# SD.net
KiCad netlist of a schematic drawn in Altium Designer
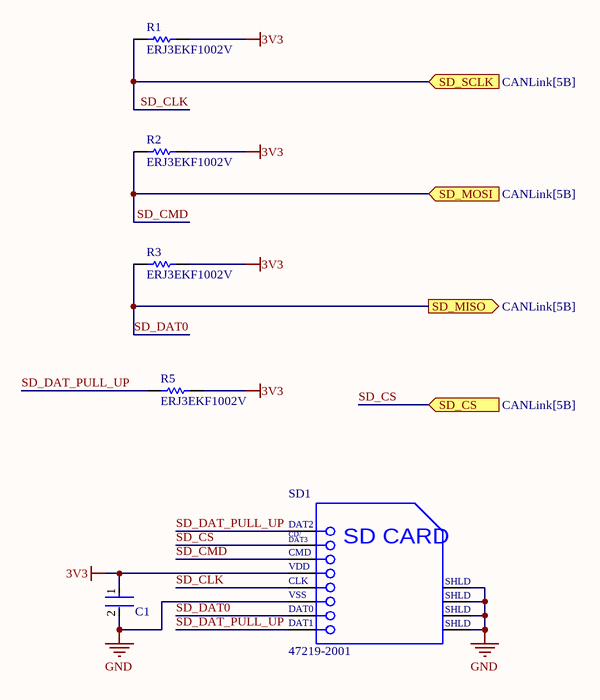
[diagram p0: SD.SchDoc]

(export (version "E")
  (design (tool "Eeschema 10.0.6"))
  (components
    (comp (ref "C1")
      (value "C0402C104K8PACTU")
      (footprint "FP-C0402-BB-MFG")
      (description "CAP CER 0.1UF 10V X5R 0402")
      (fields (field (name "MANUFACTURER") "Kemet") (field (name "TOLERANCE") "0.1"))
      (libsource (lib "Altium Content Vault") (part "b4654b650e69147ec39a6b967a45e02"))
    )
    (comp (ref "R1")
      (value "ERJ3EKF1002V")
      (footprint "RESC1609X55X30LL15T15")
      (description "Chip Resistor, 10 KOhm, +/- 1%, 0.1 W, -55 to 155 degC, 0603 (1608 Metric), RoHS, Tape and Reel")
      (fields (field (name "TOLERANCE") "1%") (field (name "MANUFACTURER") "Panasonic"))
      (libsource (lib "Altium Content Vault") (part "RES-2"))
    )
    (comp (ref "R2")
      (value "ERJ3EKF1002V")
      (footprint "RESC1609X55X30LL15T15")
      (description "Chip Resistor, 10 KOhm, +/- 1%, 0.1 W, -55 to 155 degC, 0603 (1608 Metric), RoHS, Tape and Reel")
      (fields (field (name "TOLERANCE") "1%") (field (name "MANUFACTURER") "Panasonic"))
      (libsource (lib "Altium Content Vault") (part "RES-2"))
    )
    (comp (ref "R3")
      (value "ERJ3EKF1002V")
      (footprint "RESC1609X55X30LL15T15")
      (description "Chip Resistor, 10 KOhm, +/- 1%, 0.1 W, -55 to 155 degC, 0603 (1608 Metric), RoHS, Tape and Reel")
      (fields (field (name "TOLERANCE") "1%") (field (name "MANUFACTURER") "Panasonic"))
      (libsource (lib "Altium Content Vault") (part "RES-2"))
    )
    (comp (ref "R5")
      (value "ERJ3EKF1002V")
      (footprint "RESC1609X55X30LL15T15")
      (description "Chip Resistor, 10 KOhm, +/- 1%, 0.1 W, -55 to 155 degC, 0603 (1608 Metric), RoHS, Tape and Reel")
      (fields (field (name "TOLERANCE") "1%") (field (name "MANUFACTURER") "Panasonic"))
      (libsource (lib "Altium Content Vault") (part "RES-2"))
    )
    (comp (ref "SD1")
      (value "47219-2001")
      (footprint "MOLX-47219-2001-8_V")
      (description "MicroSD Card Connector, Hinge Type, -40 to 85 degC, 8-Pin SMD, RoHS, Tape and Reel")
      (fields (field (name "MANUFACTURER") "Molex"))
      (libsource (lib "Altium Content Vault") (part "CN-SD-8-4S"))
    )
  )
  (nets
    (net (code "1") (name "/SD_CLK") (class "Default")
      (node (ref "R1") (pin "1") (pinfunction "1_1") (pintype "passive"))
      (node (ref "SD1") (pin "5") (pinfunction "CLK_5") (pintype "passive"))
    )
    (net (code "2") (name "/SD_CMD") (class "Default")
      (node (ref "R2") (pin "1") (pinfunction "1_1") (pintype "passive"))
      (node (ref "SD1") (pin "3") (pinfunction "CMD_3") (pintype "passive"))
    )
    (net (code "3") (name "/SD_CS") (class "Default")
      (node (ref "SD1") (pin "2") (pinfunction "CD/DAT3_2") (pintype "passive"))
    )
    (net (code "4") (name "/SD_DAT0") (class "Default")
      (node (ref "R3") (pin "1") (pinfunction "1_1") (pintype "passive"))
      (node (ref "SD1") (pin "7") (pinfunction "DAT0_7") (pintype "passive"))
    )
    (net (code "5") (name "/SD_DAT_PULL_UP") (class "Default")
      (node (ref "R5") (pin "1") (pinfunction "1_1") (pintype "passive"))
      (node (ref "SD1") (pin "1") (pinfunction "DAT2_1") (pintype "passive"))
      (node (ref "SD1") (pin "8") (pinfunction "DAT1_8") (pintype "passive"))
    )
    (net (code "6") (name "3V3") (class "Default")
      (node (ref "C1") (pin "1") (pinfunction "1_1") (pintype "passive"))
      (node (ref "R1") (pin "2") (pinfunction "2_2") (pintype "passive"))
      (node (ref "R2") (pin "2") (pinfunction "2_2") (pintype "passive"))
      (node (ref "R3") (pin "2") (pinfunction "2_2") (pintype "passive"))
      (node (ref "R5") (pin "2") (pinfunction "2_2") (pintype "passive"))
      (node (ref "SD1") (pin "4") (pinfunction "VDD_4") (pintype "passive"))
    )
    (net (code "7") (name "GND") (class "Default")
      (node (ref "C1") (pin "2") (pinfunction "2_2") (pintype "passive"))
      (node (ref "SD1") (pin "10") (pinfunction "SHLD_10") (pintype "passive"))
      (node (ref "SD1") (pin "11") (pinfunction "SHLD_11") (pintype "passive"))
      (node (ref "SD1") (pin "12") (pinfunction "SHLD_12") (pintype "passive"))
      (node (ref "SD1") (pin "6") (pinfunction "VSS_6") (pintype "passive"))
      (node (ref "SD1") (pin "9") (pinfunction "SHLD_9") (pintype "passive"))
    )
  )
)
